# leds-smd.net
KiCad netlist of a schematic drawn in EAGLE
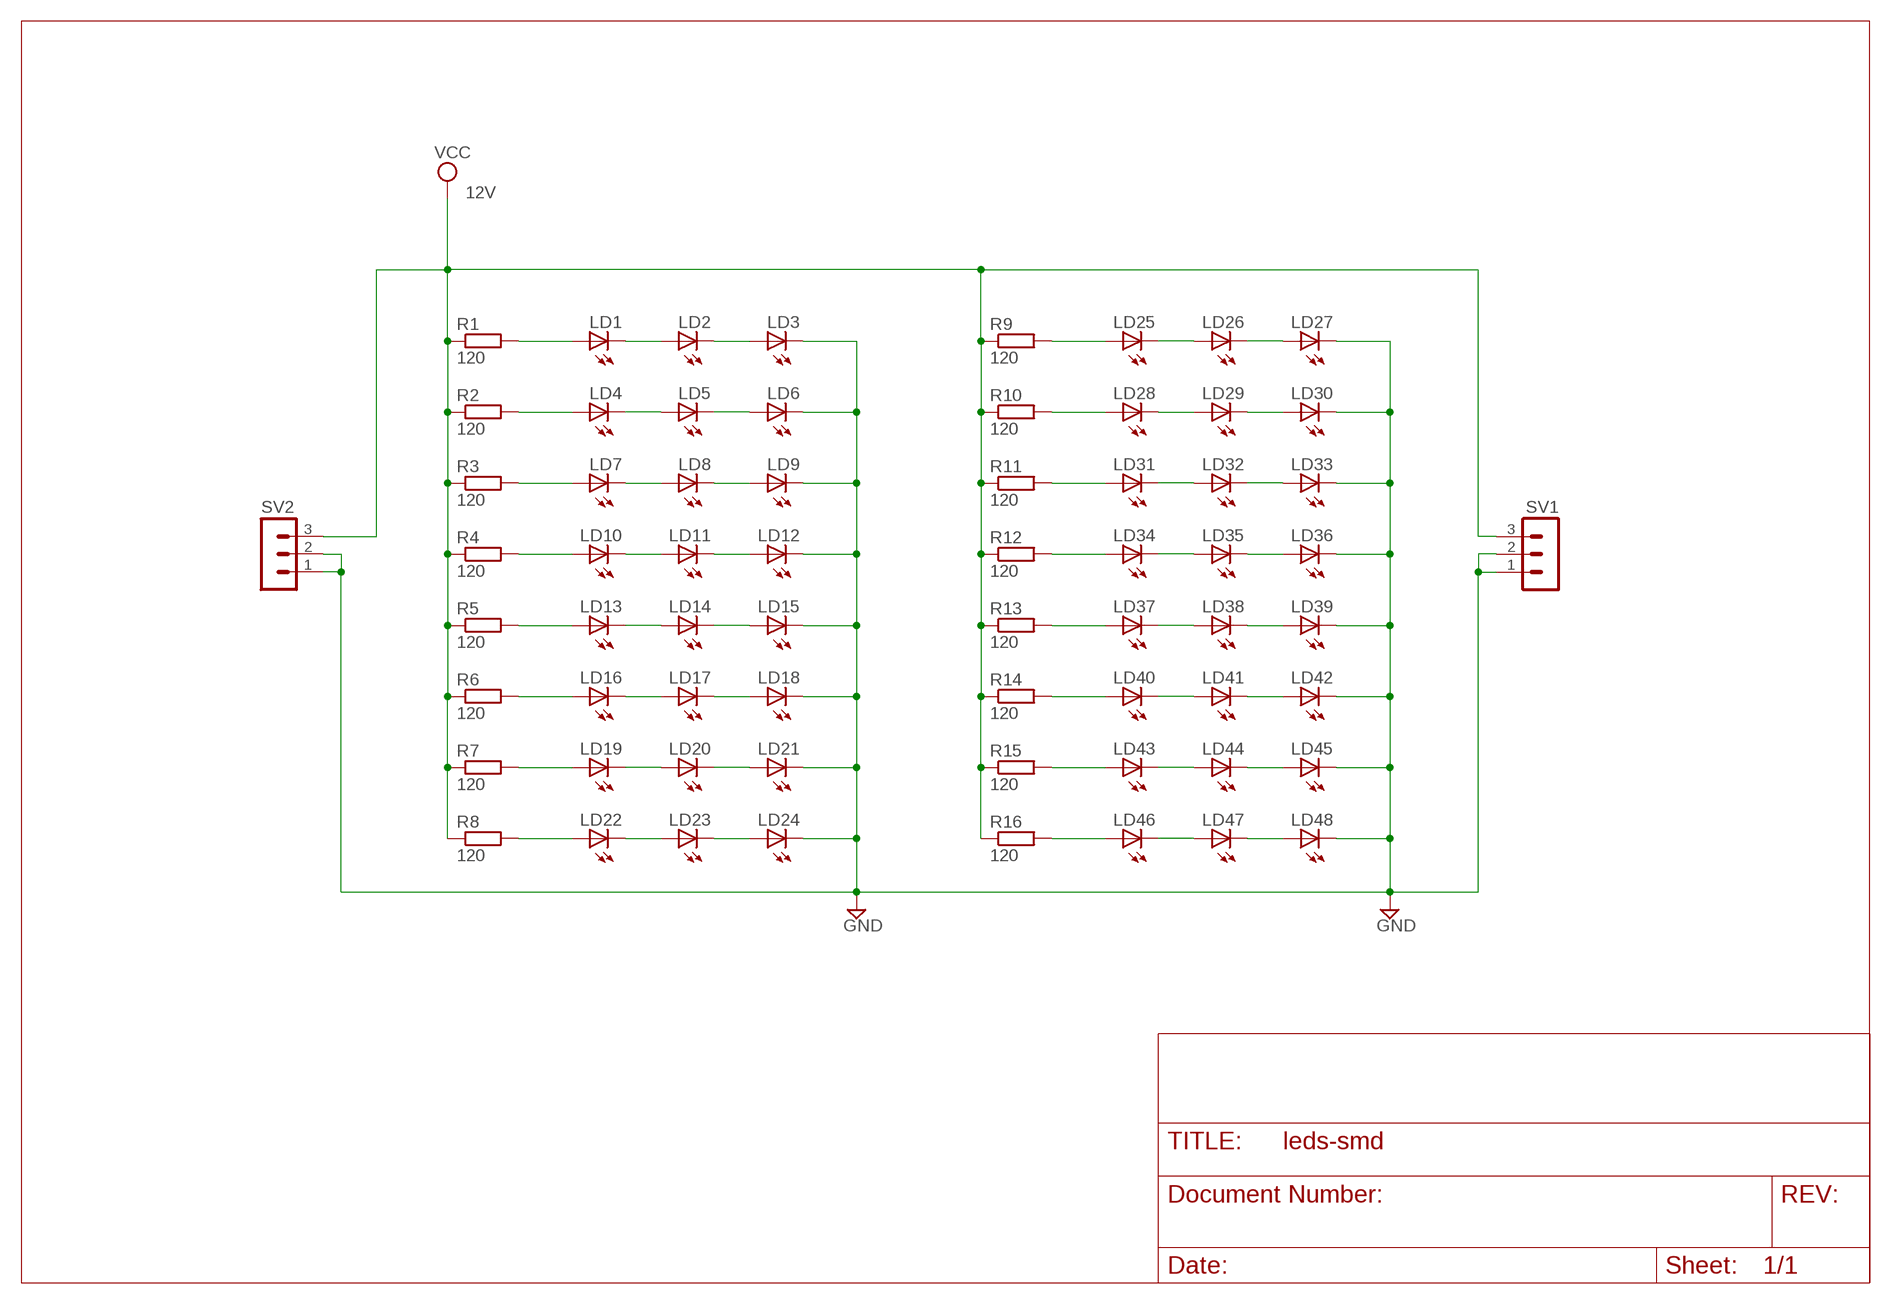
[diagram p0: schematic, sheet 1]

(export (version "E")
  (design (tool "Eeschema 10.0.6"))
  (components
    (comp (ref "LD1")
      (value "LED5MM")
      (footprint "eagle-import:LED5MM")
      (libsource (lib "eagle-import") (part "LED5MM"))
    )
    (comp (ref "LD2")
      (value "LED5MM")
      (footprint "eagle-import:LED5MM")
      (libsource (lib "eagle-import") (part "LED5MM"))
    )
    (comp (ref "LD3")
      (value "LED5MM")
      (footprint "eagle-import:LED5MM")
      (libsource (lib "eagle-import") (part "LED5MM"))
    )
    (comp (ref "LD4")
      (value "LED5MM")
      (footprint "eagle-import:LED5MM")
      (libsource (lib "eagle-import") (part "LED5MM"))
    )
    (comp (ref "LD5")
      (value "LED5MM")
      (footprint "eagle-import:LED5MM")
      (libsource (lib "eagle-import") (part "LED5MM"))
    )
    (comp (ref "LD6")
      (value "LED5MM")
      (footprint "eagle-import:LED5MM")
      (libsource (lib "eagle-import") (part "LED5MM"))
    )
    (comp (ref "LD7")
      (value "LED5MM")
      (footprint "eagle-import:LED5MM")
      (libsource (lib "eagle-import") (part "LED5MM"))
    )
    (comp (ref "LD8")
      (value "LED5MM")
      (footprint "eagle-import:LED5MM")
      (libsource (lib "eagle-import") (part "LED5MM"))
    )
    (comp (ref "LD9")
      (value "LED5MM")
      (footprint "eagle-import:LED5MM")
      (libsource (lib "eagle-import") (part "LED5MM"))
    )
    (comp (ref "LD10")
      (value "LED5MM")
      (footprint "eagle-import:LED5MM")
      (libsource (lib "eagle-import") (part "LED5MM"))
    )
    (comp (ref "LD11")
      (value "LED5MM")
      (footprint "eagle-import:LED5MM")
      (libsource (lib "eagle-import") (part "LED5MM"))
    )
    (comp (ref "LD12")
      (value "LED5MM")
      (footprint "eagle-import:LED5MM")
      (libsource (lib "eagle-import") (part "LED5MM"))
    )
    (comp (ref "LD13")
      (value "LED5MM")
      (footprint "eagle-import:LED5MM")
      (libsource (lib "eagle-import") (part "LED5MM"))
    )
    (comp (ref "LD14")
      (value "LED5MM")
      (footprint "eagle-import:LED5MM")
      (libsource (lib "eagle-import") (part "LED5MM"))
    )
    (comp (ref "LD15")
      (value "LED5MM")
      (footprint "eagle-import:LED5MM")
      (libsource (lib "eagle-import") (part "LED5MM"))
    )
    (comp (ref "LD16")
      (value "LED5MM")
      (footprint "eagle-import:LED5MM")
      (libsource (lib "eagle-import") (part "LED5MM"))
    )
    (comp (ref "LD17")
      (value "LED5MM")
      (footprint "eagle-import:LED5MM")
      (libsource (lib "eagle-import") (part "LED5MM"))
    )
    (comp (ref "LD18")
      (value "LED5MM")
      (footprint "eagle-import:LED5MM")
      (libsource (lib "eagle-import") (part "LED5MM"))
    )
    (comp (ref "LD19")
      (value "LED5MM")
      (footprint "eagle-import:LED5MM")
      (libsource (lib "eagle-import") (part "LED5MM"))
    )
    (comp (ref "LD20")
      (value "LED5MM")
      (footprint "eagle-import:LED5MM")
      (libsource (lib "eagle-import") (part "LED5MM"))
    )
    (comp (ref "LD21")
      (value "LED5MM")
      (footprint "eagle-import:LED5MM")
      (libsource (lib "eagle-import") (part "LED5MM"))
    )
    (comp (ref "LD22")
      (value "LED5MM")
      (footprint "eagle-import:LED5MM")
      (libsource (lib "eagle-import") (part "LED5MM"))
    )
    (comp (ref "LD23")
      (value "LED5MM")
      (footprint "eagle-import:LED5MM")
      (libsource (lib "eagle-import") (part "LED5MM"))
    )
    (comp (ref "LD24")
      (value "LED5MM")
      (footprint "eagle-import:LED5MM")
      (libsource (lib "eagle-import") (part "LED5MM"))
    )
    (comp (ref "LD25")
      (value "LED5MM")
      (footprint "eagle-import:LED5MM")
      (libsource (lib "eagle-import") (part "LED5MM"))
    )
    (comp (ref "LD26")
      (value "LED5MM")
      (footprint "eagle-import:LED5MM")
      (libsource (lib "eagle-import") (part "LED5MM"))
    )
    (comp (ref "LD27")
      (value "LED5MM")
      (footprint "eagle-import:LED5MM")
      (libsource (lib "eagle-import") (part "LED5MM"))
    )
    (comp (ref "LD28")
      (value "LED5MM")
      (footprint "eagle-import:LED5MM")
      (libsource (lib "eagle-import") (part "LED5MM"))
    )
    (comp (ref "LD29")
      (value "LED5MM")
      (footprint "eagle-import:LED5MM")
      (libsource (lib "eagle-import") (part "LED5MM"))
    )
    (comp (ref "LD30")
      (value "LED5MM")
      (footprint "eagle-import:LED5MM")
      (libsource (lib "eagle-import") (part "LED5MM"))
    )
    (comp (ref "LD31")
      (value "LED5MM")
      (footprint "eagle-import:LED5MM")
      (libsource (lib "eagle-import") (part "LED5MM"))
    )
    (comp (ref "LD32")
      (value "LED5MM")
      (footprint "eagle-import:LED5MM")
      (libsource (lib "eagle-import") (part "LED5MM"))
    )
    (comp (ref "LD33")
      (value "LED5MM")
      (footprint "eagle-import:LED5MM")
      (libsource (lib "eagle-import") (part "LED5MM"))
    )
    (comp (ref "LD34")
      (value "LED5MM")
      (footprint "eagle-import:LED5MM")
      (libsource (lib "eagle-import") (part "LED5MM"))
    )
    (comp (ref "LD35")
      (value "LED5MM")
      (footprint "eagle-import:LED5MM")
      (libsource (lib "eagle-import") (part "LED5MM"))
    )
    (comp (ref "LD36")
      (value "LED5MM")
      (footprint "eagle-import:LED5MM")
      (libsource (lib "eagle-import") (part "LED5MM"))
    )
    (comp (ref "LD37")
      (value "LED5MM")
      (footprint "eagle-import:LED5MM")
      (libsource (lib "eagle-import") (part "LED5MM"))
    )
    (comp (ref "LD38")
      (value "LED5MM")
      (footprint "eagle-import:LED5MM")
      (libsource (lib "eagle-import") (part "LED5MM"))
    )
    (comp (ref "LD39")
      (value "LED5MM")
      (footprint "eagle-import:LED5MM")
      (libsource (lib "eagle-import") (part "LED5MM"))
    )
    (comp (ref "LD40")
      (value "LED5MM")
      (footprint "eagle-import:LED5MM")
      (libsource (lib "eagle-import") (part "LED5MM"))
    )
    (comp (ref "LD41")
      (value "LED5MM")
      (footprint "eagle-import:LED5MM")
      (libsource (lib "eagle-import") (part "LED5MM"))
    )
    (comp (ref "LD42")
      (value "LED5MM")
      (footprint "eagle-import:LED5MM")
      (libsource (lib "eagle-import") (part "LED5MM"))
    )
    (comp (ref "LD43")
      (value "LED5MM")
      (footprint "eagle-import:LED5MM")
      (libsource (lib "eagle-import") (part "LED5MM"))
    )
    (comp (ref "LD44")
      (value "LED5MM")
      (footprint "eagle-import:LED5MM")
      (libsource (lib "eagle-import") (part "LED5MM"))
    )
    (comp (ref "LD45")
      (value "LED5MM")
      (footprint "eagle-import:LED5MM")
      (libsource (lib "eagle-import") (part "LED5MM"))
    )
    (comp (ref "LD46")
      (value "LED5MM")
      (footprint "eagle-import:LED5MM")
      (libsource (lib "eagle-import") (part "LED5MM"))
    )
    (comp (ref "LD47")
      (value "LED5MM")
      (footprint "eagle-import:LED5MM")
      (libsource (lib "eagle-import") (part "LED5MM"))
    )
    (comp (ref "LD48")
      (value "LED5MM")
      (footprint "eagle-import:LED5MM")
      (libsource (lib "eagle-import") (part "LED5MM"))
    )
    (comp (ref "R1")
      (value "120")
      (footprint "eagle-import:M1206")
      (libsource (lib "eagle-import") (part "R-EU_M1206"))
    )
    (comp (ref "R2")
      (value "120")
      (footprint "eagle-import:M1206")
      (libsource (lib "eagle-import") (part "R-EU_M1206"))
    )
    (comp (ref "R3")
      (value "120")
      (footprint "eagle-import:M1206")
      (libsource (lib "eagle-import") (part "R-EU_M1206"))
    )
    (comp (ref "R4")
      (value "120")
      (footprint "eagle-import:M1206")
      (libsource (lib "eagle-import") (part "R-EU_M1206"))
    )
    (comp (ref "R5")
      (value "120")
      (footprint "eagle-import:M1206")
      (libsource (lib "eagle-import") (part "R-EU_M1206"))
    )
    (comp (ref "R6")
      (value "120")
      (footprint "eagle-import:M1206")
      (libsource (lib "eagle-import") (part "R-EU_M1206"))
    )
    (comp (ref "R7")
      (value "120")
      (footprint "eagle-import:M1206")
      (libsource (lib "eagle-import") (part "R-EU_M1206"))
    )
    (comp (ref "R8")
      (value "120")
      (footprint "eagle-import:M1206")
      (libsource (lib "eagle-import") (part "R-EU_M1206"))
    )
    (comp (ref "R9")
      (value "120")
      (footprint "eagle-import:M1206")
      (libsource (lib "eagle-import") (part "R-EU_M1206"))
    )
    (comp (ref "R10")
      (value "120")
      (footprint "eagle-import:M1206")
      (libsource (lib "eagle-import") (part "R-EU_M1206"))
    )
    (comp (ref "R11")
      (value "120")
      (footprint "eagle-import:M1206")
      (libsource (lib "eagle-import") (part "R-EU_M1206"))
    )
    (comp (ref "R12")
      (value "120")
      (footprint "eagle-import:M1206")
      (libsource (lib "eagle-import") (part "R-EU_M1206"))
    )
    (comp (ref "R13")
      (value "120")
      (footprint "eagle-import:M1206")
      (libsource (lib "eagle-import") (part "R-EU_M1206"))
    )
    (comp (ref "R14")
      (value "120")
      (footprint "eagle-import:M1206")
      (libsource (lib "eagle-import") (part "R-EU_M1206"))
    )
    (comp (ref "R15")
      (value "120")
      (footprint "eagle-import:M1206")
      (libsource (lib "eagle-import") (part "R-EU_M1206"))
    )
    (comp (ref "R16")
      (value "120")
      (footprint "eagle-import:M1206")
      (libsource (lib "eagle-import") (part "R-EU_M1206"))
    )
    (comp (ref "SV1")
      (value "MA03-1")
      (footprint "eagle-import:MA03-1")
      (libsource (lib "eagle-import") (part "MA03-1"))
    )
    (comp (ref "SV2")
      (value "MA03-1")
      (footprint "eagle-import:MA03-1")
      (libsource (lib "eagle-import") (part "MA03-1"))
    )
  )
  (nets
    (net (code "1") (name "GND") (class "Default")
      (node (ref "LD12") (pin "K") (pinfunction "C_K") (pintype "passive"))
      (node (ref "LD15") (pin "K") (pinfunction "C_K") (pintype "passive"))
      (node (ref "LD18") (pin "K") (pinfunction "C_K") (pintype "passive"))
      (node (ref "LD21") (pin "K") (pinfunction "C_K") (pintype "passive"))
      (node (ref "LD24") (pin "K") (pinfunction "C_K") (pintype "passive"))
      (node (ref "LD27") (pin "K") (pinfunction "C_K") (pintype "passive"))
      (node (ref "LD3") (pin "K") (pinfunction "C_K") (pintype "passive"))
      (node (ref "LD30") (pin "K") (pinfunction "C_K") (pintype "passive"))
      (node (ref "LD33") (pin "K") (pinfunction "C_K") (pintype "passive"))
      (node (ref "LD36") (pin "K") (pinfunction "C_K") (pintype "passive"))
      (node (ref "LD39") (pin "K") (pinfunction "C_K") (pintype "passive"))
      (node (ref "LD42") (pin "K") (pinfunction "C_K") (pintype "passive"))
      (node (ref "LD45") (pin "K") (pinfunction "C_K") (pintype "passive"))
      (node (ref "LD48") (pin "K") (pinfunction "C_K") (pintype "passive"))
      (node (ref "LD6") (pin "K") (pinfunction "C_K") (pintype "passive"))
      (node (ref "LD9") (pin "K") (pinfunction "C_K") (pintype "passive"))
      (node (ref "SV1") (pin "1") (pinfunction "1_1") (pintype "passive"))
      (node (ref "SV1") (pin "2") (pinfunction "2_2") (pintype "passive"))
      (node (ref "SV2") (pin "1") (pinfunction "1_1") (pintype "passive"))
      (node (ref "SV2") (pin "2") (pinfunction "2_2") (pintype "passive"))
    )
    (net (code "2") (name "Net-(LD1-C)") (class "Default")
      (node (ref "LD1") (pin "K") (pinfunction "C_K") (pintype "passive"))
      (node (ref "LD2") (pin "A") (pinfunction "A_A") (pintype "passive"))
    )
    (net (code "3") (name "Net-(LD1-PadA)") (class "Default")
      (node (ref "LD1") (pin "A") (pinfunction "A_A") (pintype "passive"))
      (node (ref "R1") (pin "2") (pinfunction "2_2") (pintype "passive"))
    )
    (net (code "4") (name "Net-(LD2-C)") (class "Default")
      (node (ref "LD2") (pin "K") (pinfunction "C_K") (pintype "passive"))
      (node (ref "LD3") (pin "A") (pinfunction "A_A") (pintype "passive"))
    )
    (net (code "5") (name "Net-(LD4-C)") (class "Default")
      (node (ref "LD4") (pin "K") (pinfunction "C_K") (pintype "passive"))
      (node (ref "LD5") (pin "A") (pinfunction "A_A") (pintype "passive"))
    )
    (net (code "6") (name "Net-(LD4-PadA)") (class "Default")
      (node (ref "LD4") (pin "A") (pinfunction "A_A") (pintype "passive"))
      (node (ref "R2") (pin "2") (pinfunction "2_2") (pintype "passive"))
    )
    (net (code "7") (name "Net-(LD5-C)") (class "Default")
      (node (ref "LD5") (pin "K") (pinfunction "C_K") (pintype "passive"))
      (node (ref "LD6") (pin "A") (pinfunction "A_A") (pintype "passive"))
    )
    (net (code "8") (name "Net-(LD7-C)") (class "Default")
      (node (ref "LD7") (pin "K") (pinfunction "C_K") (pintype "passive"))
      (node (ref "LD8") (pin "A") (pinfunction "A_A") (pintype "passive"))
    )
    (net (code "9") (name "Net-(LD7-PadA)") (class "Default")
      (node (ref "LD7") (pin "A") (pinfunction "A_A") (pintype "passive"))
      (node (ref "R3") (pin "2") (pinfunction "2_2") (pintype "passive"))
    )
    (net (code "10") (name "Net-(LD8-C)") (class "Default")
      (node (ref "LD8") (pin "K") (pinfunction "C_K") (pintype "passive"))
      (node (ref "LD9") (pin "A") (pinfunction "A_A") (pintype "passive"))
    )
    (net (code "11") (name "Net-(LD10-C)") (class "Default")
      (node (ref "LD10") (pin "K") (pinfunction "C_K") (pintype "passive"))
      (node (ref "LD11") (pin "A") (pinfunction "A_A") (pintype "passive"))
    )
    (net (code "12") (name "Net-(LD10-PadA)") (class "Default")
      (node (ref "LD10") (pin "A") (pinfunction "A_A") (pintype "passive"))
      (node (ref "R4") (pin "2") (pinfunction "2_2") (pintype "passive"))
    )
    (net (code "13") (name "Net-(LD11-C)") (class "Default")
      (node (ref "LD11") (pin "K") (pinfunction "C_K") (pintype "passive"))
      (node (ref "LD12") (pin "A") (pinfunction "A_A") (pintype "passive"))
    )
    (net (code "14") (name "Net-(LD13-C)") (class "Default")
      (node (ref "LD13") (pin "K") (pinfunction "C_K") (pintype "passive"))
      (node (ref "LD14") (pin "A") (pinfunction "A_A") (pintype "passive"))
    )
    (net (code "15") (name "Net-(LD13-PadA)") (class "Default")
      (node (ref "LD13") (pin "A") (pinfunction "A_A") (pintype "passive"))
      (node (ref "R5") (pin "2") (pinfunction "2_2") (pintype "passive"))
    )
    (net (code "16") (name "Net-(LD14-C)") (class "Default")
      (node (ref "LD14") (pin "K") (pinfunction "C_K") (pintype "passive"))
      (node (ref "LD15") (pin "A") (pinfunction "A_A") (pintype "passive"))
    )
    (net (code "17") (name "Net-(LD16-C)") (class "Default")
      (node (ref "LD16") (pin "K") (pinfunction "C_K") (pintype "passive"))
      (node (ref "LD17") (pin "A") (pinfunction "A_A") (pintype "passive"))
    )
    (net (code "18") (name "Net-(LD16-PadA)") (class "Default")
      (node (ref "LD16") (pin "A") (pinfunction "A_A") (pintype "passive"))
      (node (ref "R6") (pin "2") (pinfunction "2_2") (pintype "passive"))
    )
    (net (code "19") (name "Net-(LD17-C)") (class "Default")
      (node (ref "LD17") (pin "K") (pinfunction "C_K") (pintype "passive"))
      (node (ref "LD18") (pin "A") (pinfunction "A_A") (pintype "passive"))
    )
    (net (code "20") (name "Net-(LD19-C)") (class "Default")
      (node (ref "LD19") (pin "K") (pinfunction "C_K") (pintype "passive"))
      (node (ref "LD20") (pin "A") (pinfunction "A_A") (pintype "passive"))
    )
    (net (code "21") (name "Net-(LD19-PadA)") (class "Default")
      (node (ref "LD19") (pin "A") (pinfunction "A_A") (pintype "passive"))
      (node (ref "R7") (pin "2") (pinfunction "2_2") (pintype "passive"))
    )
    (net (code "22") (name "Net-(LD20-C)") (class "Default")
      (node (ref "LD20") (pin "K") (pinfunction "C_K") (pintype "passive"))
      (node (ref "LD21") (pin "A") (pinfunction "A_A") (pintype "passive"))
    )
    (net (code "23") (name "Net-(LD22-C)") (class "Default")
      (node (ref "LD22") (pin "K") (pinfunction "C_K") (pintype "passive"))
      (node (ref "LD23") (pin "A") (pinfunction "A_A") (pintype "passive"))
    )
    (net (code "24") (name "Net-(LD22-PadA)") (class "Default")
      (node (ref "LD22") (pin "A") (pinfunction "A_A") (pintype "passive"))
      (node (ref "R8") (pin "2") (pinfunction "2_2") (pintype "passive"))
    )
    (net (code "25") (name "Net-(LD23-C)") (class "Default")
      (node (ref "LD23") (pin "K") (pinfunction "C_K") (pintype "passive"))
      (node (ref "LD24") (pin "A") (pinfunction "A_A") (pintype "passive"))
    )
    (net (code "26") (name "Net-(LD25-C)") (class "Default")
      (node (ref "LD25") (pin "K") (pinfunction "C_K") (pintype "passive"))
      (node (ref "LD26") (pin "A") (pinfunction "A_A") (pintype "passive"))
    )
    (net (code "27") (name "Net-(LD25-PadA)") (class "Default")
      (node (ref "LD25") (pin "A") (pinfunction "A_A") (pintype "passive"))
      (node (ref "R9") (pin "2") (pinfunction "2_2") (pintype "passive"))
    )
    (net (code "28") (name "Net-(LD26-C)") (class "Default")
      (node (ref "LD26") (pin "K") (pinfunction "C_K") (pintype "passive"))
      (node (ref "LD27") (pin "A") (pinfunction "A_A") (pintype "passive"))
    )
    (net (code "29") (name "Net-(LD28-C)") (class "Default")
      (node (ref "LD28") (pin "K") (pinfunction "C_K") (pintype "passive"))
      (node (ref "LD29") (pin "A") (pinfunction "A_A") (pintype "passive"))
    )
    (net (code "30") (name "Net-(LD28-PadA)") (class "Default")
      (node (ref "LD28") (pin "A") (pinfunction "A_A") (pintype "passive"))
      (node (ref "R10") (pin "2") (pinfunction "2_2") (pintype "passive"))
    )
    (net (code "31") (name "Net-(LD29-C)") (class "Default")
      (node (ref "LD29") (pin "K") (pinfunction "C_K") (pintype "passive"))
      (node (ref "LD30") (pin "A") (pinfunction "A_A") (pintype "passive"))
    )
    (net (code "32") (name "Net-(LD31-C)") (class "Default")
      (node (ref "LD31") (pin "K") (pinfunction "C_K") (pintype "passive"))
      (node (ref "LD32") (pin "A") (pinfunction "A_A") (pintype "passive"))
    )
    (net (code "33") (name "Net-(LD31-PadA)") (class "Default")
      (node (ref "LD31") (pin "A") (pinfunction "A_A") (pintype "passive"))
      (node (ref "R11") (pin "2") (pinfunction "2_2") (pintype "passive"))
    )
    (net (code "34") (name "Net-(LD32-C)") (class "Default")
      (node (ref "LD32") (pin "K") (pinfunction "C_K") (pintype "passive"))
      (node (ref "LD33") (pin "A") (pinfunction "A_A") (pintype "passive"))
    )
    (net (code "35") (name "Net-(LD34-C)") (class "Default")
      (node (ref "LD34") (pin "K") (pinfunction "C_K") (pintype "passive"))
      (node (ref "LD35") (pin "A") (pinfunction "A_A") (pintype "passive"))
    )
    (net (code "36") (name "Net-(LD34-PadA)") (class "Default")
      (node (ref "LD34") (pin "A") (pinfunction "A_A") (pintype "passive"))
      (node (ref "R12") (pin "2") (pinfunction "2_2") (pintype "passive"))
    )
    (net (code "37") (name "Net-(LD35-C)") (class "Default")
      (node (ref "LD35") (pin "K") (pinfunction "C_K") (pintype "passive"))
      (node (ref "LD36") (pin "A") (pinfunction "A_A") (pintype "passive"))
    )
    (net (code "38") (name "Net-(LD37-C)") (class "Default")
      (node (ref "LD37") (pin "K") (pinfunction "C_K") (pintype "passive"))
      (node (ref "LD38") (pin "A") (pinfunction "A_A") (pintype "passive"))
    )
    (net (code "39") (name "Net-(LD37-PadA)") (class "Default")
      (node (ref "LD37") (pin "A") (pinfunction "A_A") (pintype "passive"))
      (node (ref "R13") (pin "2") (pinfunction "2_2") (pintype "passive"))
    )
    (net (code "40") (name "Net-(LD38-C)") (class "Default")
      (node (ref "LD38") (pin "K") (pinfunction "C_K") (pintype "passive"))
      (node (ref "LD39") (pin "A") (pinfunction "A_A") (pintype "passive"))
    )
    (net (code "41") (name "Net-(LD40-C)") (class "Default")
      (node (ref "LD40") (pin "K") (pinfunction "C_K") (pintype "passive"))
      (node (ref "LD41") (pin "A") (pinfunction "A_A") (pintype "passive"))
    )
    (net (code "42") (name "Net-(LD40-PadA)") (class "Default")
      (node (ref "LD40") (pin "A") (pinfunction "A_A") (pintype "passive"))
      (node (ref "R14") (pin "2") (pinfunction "2_2") (pintype "passive"))
    )
    (net (code "43") (name "Net-(LD41-C)") (class "Default")
      (node (ref "LD41") (pin "K") (pinfunction "C_K") (pintype "passive"))
      (node (ref "LD42") (pin "A") (pinfunction "A_A") (pintype "passive"))
    )
    (net (code "44") (name "Net-(LD43-C)") (class "Default")
      (node (ref "LD43") (pin "K") (pinfunction "C_K") (pintype "passive"))
      (node (ref "LD44") (pin "A") (pinfunction "A_A") (pintype "passive"))
    )
    (net (code "45") (name "Net-(LD43-PadA)") (class "Default")
      (node (ref "LD43") (pin "A") (pinfunction "A_A") (pintype "passive"))
      (node (ref "R15") (pin "2") (pinfunction "2_2") (pintype "passive"))
    )
    (net (code "46") (name "Net-(LD44-C)") (class "Default")
      (node (ref "LD44") (pin "K") (pinfunction "C_K") (pintype "passive"))
      (node (ref "LD45") (pin "A") (pinfunction "A_A") (pintype "passive"))
    )
    (net (code "47") (name "Net-(LD46-C)") (class "Default")
      (node (ref "LD46") (pin "K") (pinfunction "C_K") (pintype "passive"))
      (node (ref "LD47") (pin "A") (pinfunction "A_A") (pintype "passive"))
    )
    (net (code "48") (name "Net-(LD46-PadA)") (class "Default")
      (node (ref "LD46") (pin "A") (pinfunction "A_A") (pintype "passive"))
      (node (ref "R16") (pin "2") (pinfunction "2_2") (pintype "passive"))
    )
    (net (code "49") (name "Net-(LD47-C)") (class "Default")
      (node (ref "LD47") (pin "K") (pinfunction "C_K") (pintype "passive"))
      (node (ref "LD48") (pin "A") (pinfunction "A_A") (pintype "passive"))
    )
    (net (code "50") (name "VCC") (class "Default")
      (node (ref "R1") (pin "1") (pinfunction "1_1") (pintype "passive"))
      (node (ref "R10") (pin "1") (pinfunction "1_1") (pintype "passive"))
      (node (ref "R11") (pin "1") (pinfunction "1_1") (pintype "passive"))
      (node (ref "R12") (pin "1") (pinfunction "1_1") (pintype "passive"))
      (node (ref "R13") (pin "1") (pinfunction "1_1") (pintype "passive"))
      (node (ref "R14") (pin "1") (pinfunction "1_1") (pintype "passive"))
      (node (ref "R15") (pin "1") (pinfunction "1_1") (pintype "passive"))
      (node (ref "R16") (pin "1") (pinfunction "1_1") (pintype "passive"))
      (node (ref "R2") (pin "1") (pinfunction "1_1") (pintype "passive"))
      (node (ref "R3") (pin "1") (pinfunction "1_1") (pintype "passive"))
      (node (ref "R4") (pin "1") (pinfunction "1_1") (pintype "passive"))
      (node (ref "R5") (pin "1") (pinfunction "1_1") (pintype "passive"))
      (node (ref "R6") (pin "1") (pinfunction "1_1") (pintype "passive"))
      (node (ref "R7") (pin "1") (pinfunction "1_1") (pintype "passive"))
      (node (ref "R8") (pin "1") (pinfunction "1_1") (pintype "passive"))
      (node (ref "R9") (pin "1") (pinfunction "1_1") (pintype "passive"))
      (node (ref "SV1") (pin "3") (pinfunction "3_3") (pintype "passive"))
      (node (ref "SV2") (pin "3") (pinfunction "3_3") (pintype "passive"))
    )
  )
)
